# MDQARM_USB_UART.net
KiCad netlist of a schematic drawn in Altium Designer
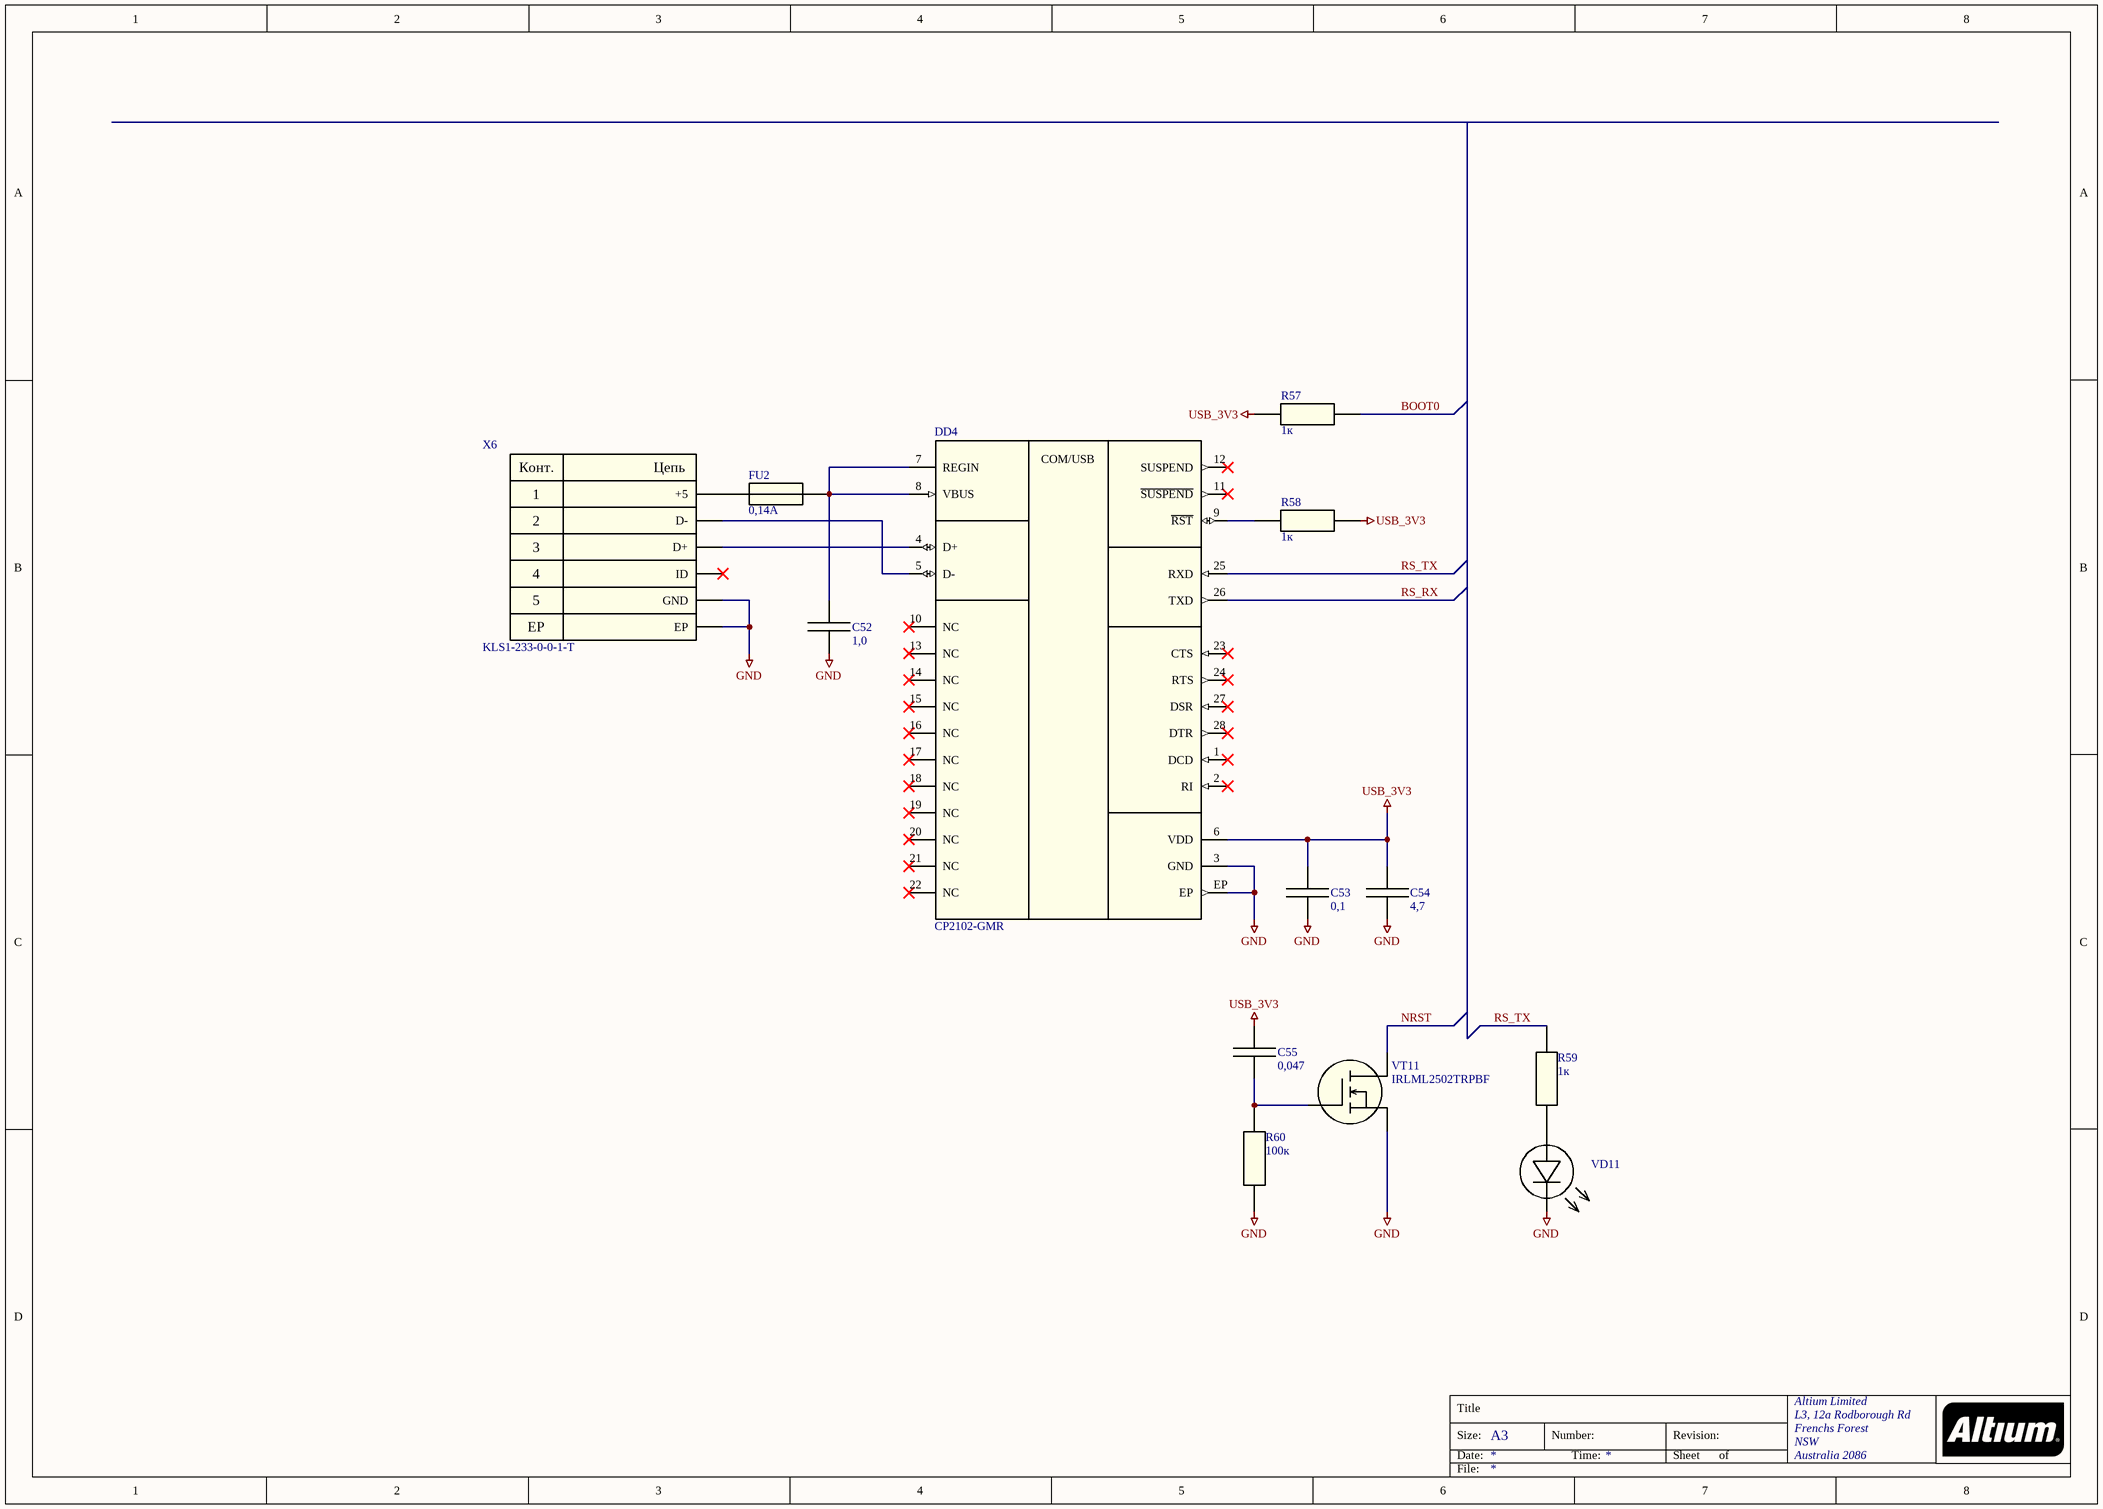
[diagram p0: MDQARM_USB_UART.SchDoc]

(export (version "E")
  (design (tool "Eeschema 10.0.6"))
  (components
    (comp (ref "C52")
      (value "1,0")
      (footprint "Capacitor SMD0805-T1.35")
      (libsource (lib "IVV_Passive") (part "Capacitor C0805_1u"))
    )
    (comp (ref "C53")
      (value "0,1")
      (footprint "Capacitor SMD0805-T0.95")
      (libsource (lib "IVV_Passive") (part "Capacitor C0805_100n"))
    )
    (comp (ref "C54")
      (value "4,7")
      (footprint "Capacitor SMD0805-T1.35")
      (libsource (lib "IVV_Passive") (part "Capacitor C0805_4.7u"))
    )
    (comp (ref "C55")
      (value "0,047")
      (footprint "Capacitor SMD0805-T0.75")
      (libsource (lib "IVV_Passive") (part "Capacitor C0805_47n"))
    )
    (comp (ref "DD4")
      (value "CP2102-GMR")
      (footprint "IC CP2102-GMR")
      (libsource (lib "IVV_IC") (part "IC CP2102-GMR"))
    )
    (comp (ref "FU2")
      (value "0,14А")
      (footprint "Fuse MF-NSMF")
      (libsource (lib "IVV_Lib") (part "Fuse MF-NSMF014-2"))
    )
    (comp (ref "R57")
      (value "1к")
      (footprint "Resistor SMD0805")
      (libsource (lib "") (part "Resistor R0805_1k_5%_1"))
    )
    (comp (ref "R58")
      (value "1к")
      (footprint "Resistor SMD0805")
      (libsource (lib "") (part "Resistor R0805_1k_5%_2"))
    )
    (comp (ref "R59")
      (value "1к")
      (footprint "Resistor SMD0805")
      (libsource (lib "IVV_Passive") (part "Resistor R0805_1k_5%"))
    )
    (comp (ref "R60")
      (value "100к")
      (footprint "Resistor SMD0805")
      (libsource (lib "IVV_Passive") (part "Resistor R0805_100k_5%"))
    )
    (comp (ref "VD11")
      (value "GREEN")
      (footprint "Diode SMD0805")
      (description "LED Green SMD0805")
      (libsource (lib "IVV_Lib") (part "Diode LED0805GREEN"))
    )
    (comp (ref "VT11")
      (value "IRLML2502TRPBF")
      (footprint "Transistor SOT23")
      (libsource (lib "IVV_Lib") (part "Transistor IRLML2502TRPBF"))
    )
    (comp (ref "X6")
      (value "KLS1-233-0-0-1-T")
      (footprint "Connector KLS1-233-0-0-1-T")
      (description "microUSB Connector")
      (libsource (lib "IVV_Connectors") (part "Connector KLS1-233-0-0-1-T"))
    )
  )
  (nets
    (net (code "1") (name "/BOOT0") (class "Default")
      (node (ref "R57") (pin "1") (pinfunction "1_1") (pintype "passive"))
    )
    (net (code "2") (name "/NRST") (class "Default")
      (node (ref "VT11") (pin "3") (pinfunction "D_3") (pintype "passive"))
    )
    (net (code "3") (name "/RS_RX") (class "Default")
      (node (ref "DD4") (pin "26") (pinfunction "TXD_26") (pintype "output"))
    )
    (net (code "4") (name "/RS_TX") (class "Default")
      (node (ref "DD4") (pin "25") (pinfunction "RXD_25") (pintype "input"))
      (node (ref "R59") (pin "1") (pinfunction "1_1") (pintype "passive"))
    )
    (net (code "5") (name "GND") (class "Default")
      (node (ref "C52") (pin "1") (pinfunction "1_1") (pintype "passive"))
      (node (ref "C53") (pin "1") (pinfunction "1_1") (pintype "passive"))
      (node (ref "C54") (pin "1") (pinfunction "1_1") (pintype "passive"))
      (node (ref "DD4") (pin "3") (pinfunction "GND_3") (pintype "power_in"))
      (node (ref "DD4") (pin "EP") (pinfunction "EP_EP") (pintype "output"))
      (node (ref "R60") (pin "1") (pinfunction "1_1") (pintype "passive"))
      (node (ref "VD11") (pin "2") (pinfunction "C_2") (pintype "passive"))
      (node (ref "VT11") (pin "2") (pinfunction "S_2") (pintype "passive"))
      (node (ref "X6") (pin "5") (pinfunction "GND_5") (pintype "passive"))
      (node (ref "X6") (pin "EP") (pinfunction "EP_EP") (pintype "passive"))
    )
    (net (code "6") (name "Net-(DD4-D+)") (class "Default")
      (node (ref "DD4") (pin "4") (pinfunction "D+_4") (pintype "bidirectional"))
      (node (ref "X6") (pin "3") (pinfunction "D+_3") (pintype "passive"))
    )
    (net (code "7") (name "Net-(DD4-D-)") (class "Default")
      (node (ref "DD4") (pin "5") (pinfunction "D-_5") (pintype "bidirectional"))
      (node (ref "X6") (pin "2") (pinfunction "D-_2") (pintype "passive"))
    )
    (net (code "8") (name "Net-(DD4-REGIN)") (class "Default")
      (node (ref "C52") (pin "2") (pinfunction "2_2") (pintype "passive"))
      (node (ref "DD4") (pin "7") (pinfunction "REGIN_7") (pintype "power_in"))
      (node (ref "DD4") (pin "8") (pinfunction "VBUS_8") (pintype "input"))
      (node (ref "FU2") (pin "2") (pinfunction "2_2") (pintype "passive"))
    )
    (net (code "9") (name "Net-(DD4-~{RST})") (class "Default")
      (node (ref "DD4") (pin "9") (pinfunction "~{RST}_9") (pintype "bidirectional"))
      (node (ref "R58") (pin "1") (pinfunction "1_1") (pintype "passive"))
    )
    (net (code "10") (name "Net-(VD11-A)") (class "Default")
      (node (ref "R59") (pin "2") (pinfunction "2_2") (pintype "passive"))
      (node (ref "VD11") (pin "1") (pinfunction "A_1") (pintype "passive"))
    )
    (net (code "11") (name "Net-(VT11-G)") (class "Default")
      (node (ref "C55") (pin "1") (pinfunction "1_1") (pintype "passive"))
      (node (ref "R60") (pin "2") (pinfunction "2_2") (pintype "passive"))
      (node (ref "VT11") (pin "1") (pinfunction "G_1") (pintype "passive"))
    )
    (net (code "12") (name "Net-(X6-+5)") (class "Default")
      (node (ref "FU2") (pin "1") (pinfunction "1_1") (pintype "passive"))
      (node (ref "X6") (pin "1") (pinfunction "+5_1") (pintype "passive"))
    )
    (net (code "13") (name "USB_3V3") (class "Default")
      (node (ref "C53") (pin "2") (pinfunction "2_2") (pintype "passive"))
      (node (ref "C54") (pin "2") (pinfunction "2_2") (pintype "passive"))
      (node (ref "C55") (pin "2") (pinfunction "2_2") (pintype "passive"))
      (node (ref "DD4") (pin "6") (pinfunction "VDD_6") (pintype "power_in"))
      (node (ref "R57") (pin "2") (pinfunction "2_2") (pintype "passive"))
      (node (ref "R58") (pin "2") (pinfunction "2_2") (pintype "passive"))
    )
    (net (code "14") (name "unconnected-(DD4-CTS-Pad23)") (class "Default")
      (node (ref "DD4") (pin "23") (pinfunction "CTS_23") (pintype "input+no_connect"))
    )
    (net (code "15") (name "unconnected-(DD4-DCD-Pad1)") (class "Default")
      (node (ref "DD4") (pin "1") (pinfunction "DCD_1") (pintype "input+no_connect"))
    )
    (net (code "16") (name "unconnected-(DD4-DSR-Pad27)") (class "Default")
      (node (ref "DD4") (pin "27") (pinfunction "DSR_27") (pintype "input+no_connect"))
    )
    (net (code "17") (name "unconnected-(DD4-DTR-Pad28)") (class "Default")
      (node (ref "DD4") (pin "28") (pinfunction "DTR_28") (pintype "output+no_connect"))
    )
    (net (code "18") (name "unconnected-(DD4-NC-Pad10)") (class "Default")
      (node (ref "DD4") (pin "10") (pinfunction "NC_10") (pintype "passive+no_connect"))
    )
    (net (code "19") (name "unconnected-(DD4-NC-Pad13)") (class "Default")
      (node (ref "DD4") (pin "13") (pinfunction "NC_13") (pintype "passive+no_connect"))
    )
    (net (code "20") (name "unconnected-(DD4-NC-Pad14)") (class "Default")
      (node (ref "DD4") (pin "14") (pinfunction "NC_14") (pintype "passive+no_connect"))
    )
    (net (code "21") (name "unconnected-(DD4-NC-Pad15)") (class "Default")
      (node (ref "DD4") (pin "15") (pinfunction "NC_15") (pintype "passive+no_connect"))
    )
    (net (code "22") (name "unconnected-(DD4-NC-Pad16)") (class "Default")
      (node (ref "DD4") (pin "16") (pinfunction "NC_16") (pintype "passive+no_connect"))
    )
    (net (code "23") (name "unconnected-(DD4-NC-Pad17)") (class "Default")
      (node (ref "DD4") (pin "17") (pinfunction "NC_17") (pintype "passive+no_connect"))
    )
    (net (code "24") (name "unconnected-(DD4-NC-Pad18)") (class "Default")
      (node (ref "DD4") (pin "18") (pinfunction "NC_18") (pintype "passive+no_connect"))
    )
    (net (code "25") (name "unconnected-(DD4-NC-Pad19)") (class "Default")
      (node (ref "DD4") (pin "19") (pinfunction "NC_19") (pintype "passive+no_connect"))
    )
    (net (code "26") (name "unconnected-(DD4-NC-Pad20)") (class "Default")
      (node (ref "DD4") (pin "20") (pinfunction "NC_20") (pintype "passive+no_connect"))
    )
    (net (code "27") (name "unconnected-(DD4-NC-Pad21)") (class "Default")
      (node (ref "DD4") (pin "21") (pinfunction "NC_21") (pintype "passive+no_connect"))
    )
    (net (code "28") (name "unconnected-(DD4-NC-Pad22)") (class "Default")
      (node (ref "DD4") (pin "22") (pinfunction "NC_22") (pintype "passive+no_connect"))
    )
    (net (code "29") (name "unconnected-(DD4-RI-Pad2)") (class "Default")
      (node (ref "DD4") (pin "2") (pinfunction "RI_2") (pintype "input+no_connect"))
    )
    (net (code "30") (name "unconnected-(DD4-RTS-Pad24)") (class "Default")
      (node (ref "DD4") (pin "24") (pinfunction "RTS_24") (pintype "output+no_connect"))
    )
    (net (code "31") (name "unconnected-(DD4-SUSPEND-Pad12)") (class "Default")
      (node (ref "DD4") (pin "12") (pinfunction "SUSPEND_12") (pintype "output+no_connect"))
    )
    (net (code "32") (name "unconnected-(DD4-~{SUSPEND}-Pad11)") (class "Default")
      (node (ref "DD4") (pin "11") (pinfunction "~{SUSPEND}_11") (pintype "output+no_connect"))
    )
    (net (code "33") (name "unconnected-(X6-ID-Pad4)") (class "Default")
      (node (ref "X6") (pin "4") (pinfunction "ID_4") (pintype "passive+no_connect"))
    )
  )
)
